# caretaker-rotaryknob.net
KiCad netlist of a schematic drawn in EAGLE
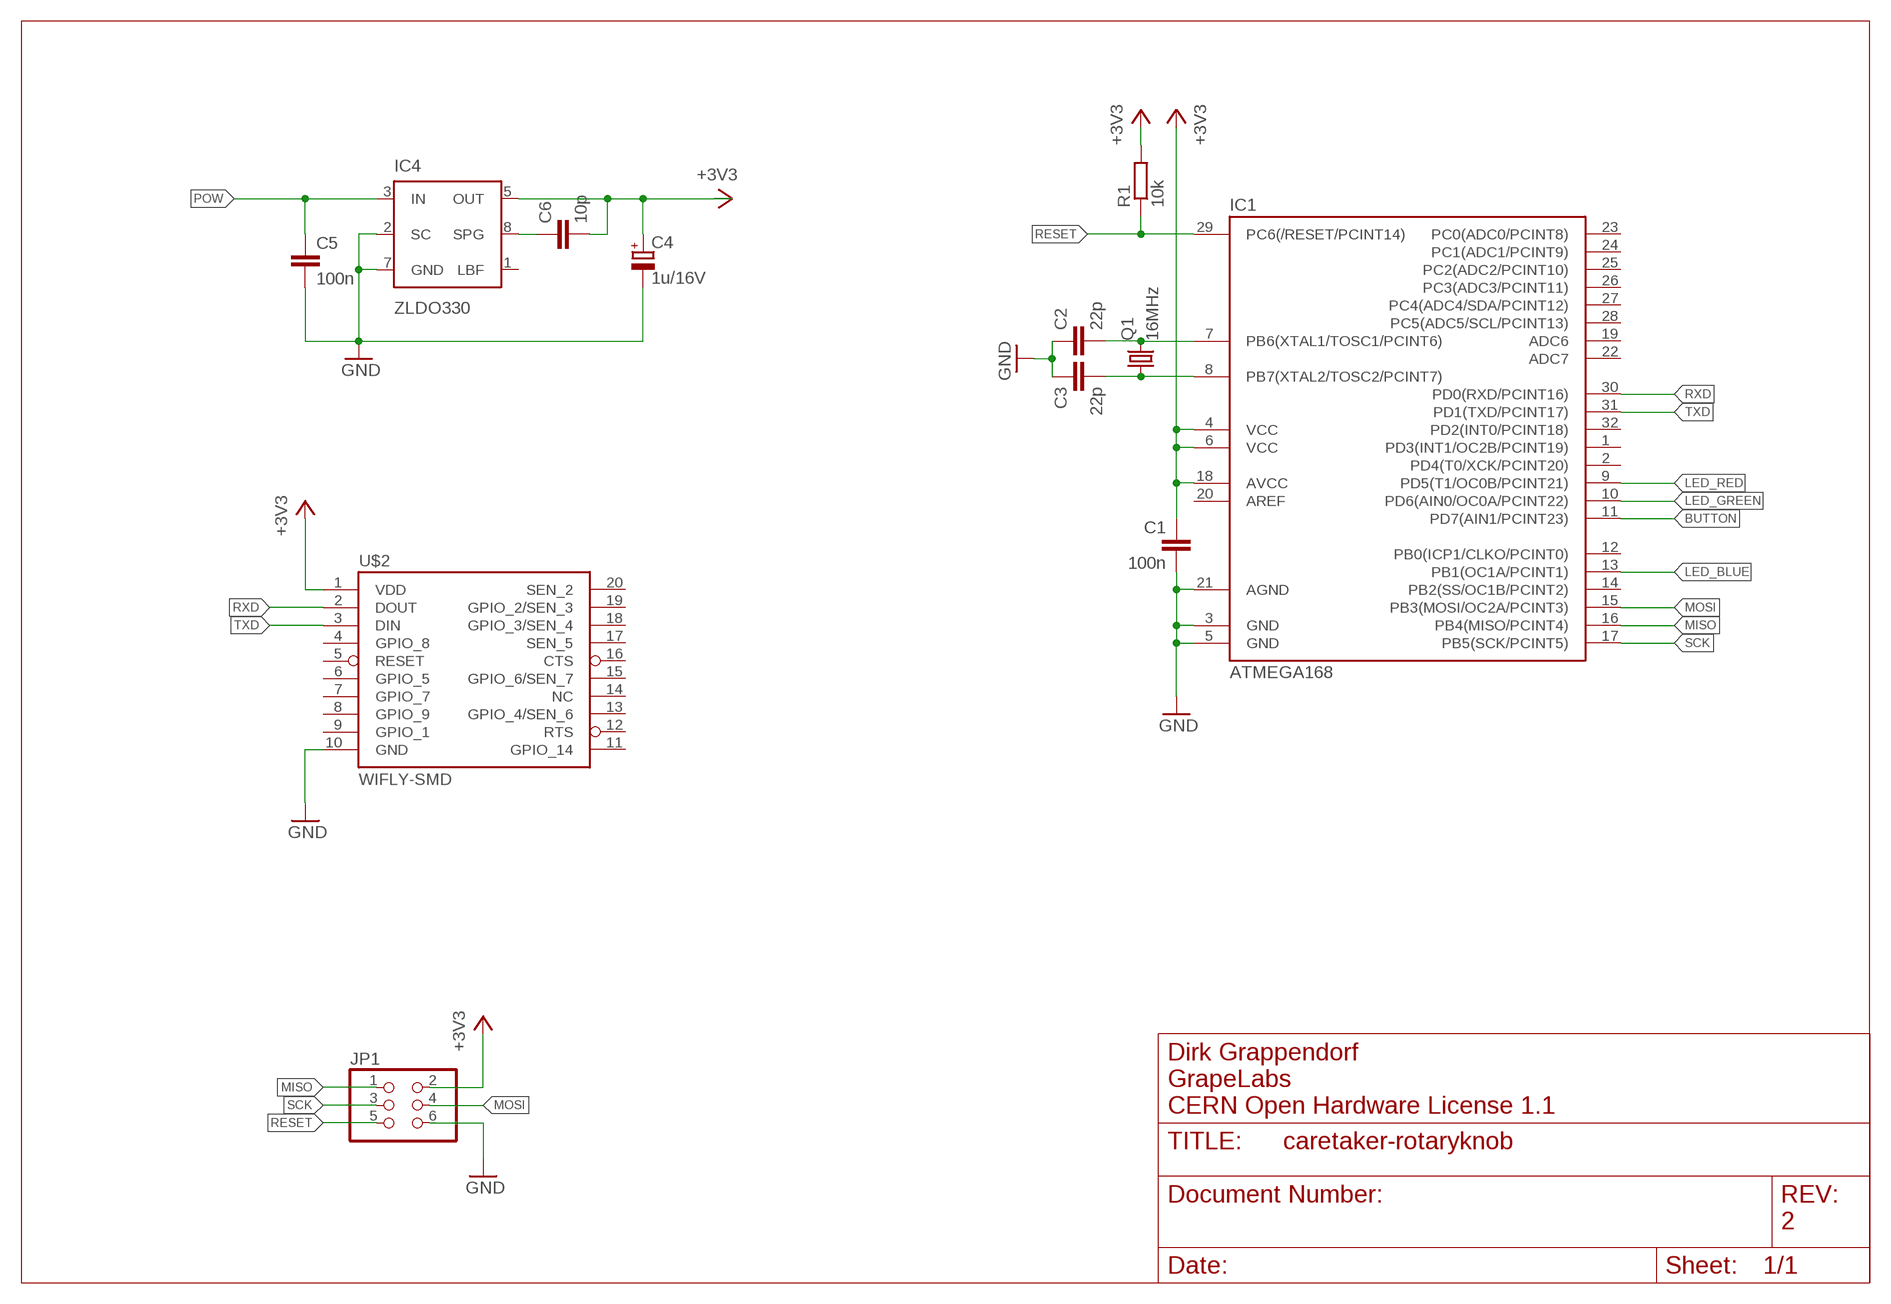
[diagram p0: schematic, sheet 1]

(export (version "E")
  (design (tool "Eeschema 10.0.6"))
  (components
    (comp (ref "C1")
      (value "100n")
      (footprint "eagle-import:C1206K")
      (libsource (lib "eagle-import") (part "C-EUC1206K"))
    )
    (comp (ref "C2")
      (value "22p")
      (footprint "eagle-import:C1206K")
      (libsource (lib "eagle-import") (part "C-EUC1206K"))
    )
    (comp (ref "C3")
      (value "22p")
      (footprint "eagle-import:C1206K")
      (libsource (lib "eagle-import") (part "C-EUC1206K"))
    )
    (comp (ref "C4")
      (value "1u/16V")
      (footprint "eagle-import:PANASONIC_B")
      (libsource (lib "eagle-import") (part "CPOL-EUB"))
    )
    (comp (ref "C5")
      (value "100n")
      (footprint "eagle-import:C1206")
      (libsource (lib "eagle-import") (part "C-EUC1206"))
    )
    (comp (ref "C6")
      (value "10p")
      (footprint "eagle-import:C1206")
      (libsource (lib "eagle-import") (part "C-EUC1206"))
    )
    (comp (ref "IC1")
      (value "ATMEGA168")
      (footprint "eagle-import:TQFP32-08")
      (libsource (lib "eagle-import") (part "ATMEGA48/88/168-AU"))
    )
    (comp (ref "IC4")
      (value "ZLDO330")
      (footprint "eagle-import:SM8")
      (libsource (lib "eagle-import") (part "ZLDO330"))
    )
    (comp (ref "JP1")
      (value "PINHD-2X3_2.54-SMD")
      (footprint "eagle-import:2X03SMD")
      (libsource (lib "eagle-import") (part "PINHD-2X3_2.54-SMD"))
    )
    (comp (ref "Q1")
      (value "16MHz")
      (footprint "eagle-import:HC49UP")
      (libsource (lib "eagle-import") (part "CRYSTALHC49UP"))
    )
    (comp (ref "R1")
      (value "10k")
      (footprint "eagle-import:M1206")
      (libsource (lib "eagle-import") (part "R-EU_M1206"))
    )
    (comp (ref "U$2")
      (value "WIFLY-SMD")
      (footprint "eagle-import:WIFLY-SMD")
      (libsource (lib "eagle-import") (part "WIFLY-SMD"))
    )
  )
  (nets
    (net (code "1") (name "+3V3") (class "Default")
      (node (ref "C1") (pin "1") (pinfunction "1_1") (pintype "passive"))
      (node (ref "C4") (pin "+") (pinfunction "+_+") (pintype "passive"))
      (node (ref "C6") (pin "2") (pinfunction "2_2") (pintype "passive"))
      (node (ref "IC1") (pin "18") (pinfunction "AVCC_18") (pintype "passive"))
      (node (ref "IC1") (pin "4") (pinfunction "VCC_4") (pintype "power_in"))
      (node (ref "IC1") (pin "6") (pinfunction "VCC_6") (pintype "power_in"))
      (node (ref "IC4") (pin "5") (pinfunction "OUT_5") (pintype "output"))
      (node (ref "JP1") (pin "2") (pinfunction "2_2") (pintype "passive"))
      (node (ref "R1") (pin "2") (pinfunction "2_2") (pintype "passive"))
      (node (ref "U$2") (pin "1") (pinfunction "VDD_1") (pintype "power_in"))
    )
    (net (code "2") (name "BUTTON") (class "Default")
      (node (ref "IC1") (pin "11") (pinfunction "PD7(AIN1/PCINT23)_11") (pintype "bidirectional"))
    )
    (net (code "3") (name "GND") (class "Default")
      (node (ref "C1") (pin "2") (pinfunction "2_2") (pintype "passive"))
      (node (ref "C2") (pin "1") (pinfunction "1_1") (pintype "passive"))
      (node (ref "C3") (pin "1") (pinfunction "1_1") (pintype "passive"))
      (node (ref "C4") (pin "-") (pinfunction "-_-") (pintype "passive"))
      (node (ref "C5") (pin "2") (pinfunction "2_2") (pintype "passive"))
      (node (ref "IC1") (pin "21") (pinfunction "AGND_21") (pintype "power_in"))
      (node (ref "IC1") (pin "3") (pinfunction "GND_3") (pintype "power_in"))
      (node (ref "IC1") (pin "5") (pinfunction "GND_5") (pintype "power_in"))
      (node (ref "IC4") (pin "2") (pinfunction "SC_2") (pintype "input"))
      (node (ref "IC4") (pin "7") (pinfunction "GND_7") (pintype "power_in"))
      (node (ref "JP1") (pin "6") (pinfunction "6_6") (pintype "passive"))
      (node (ref "U$2") (pin "10") (pinfunction "GND_10") (pintype "power_in"))
    )
    (net (code "4") (name "LED_BLUE") (class "Default")
      (node (ref "IC1") (pin "13") (pinfunction "PB1(OC1A/PCINT1)_13") (pintype "bidirectional"))
    )
    (net (code "5") (name "LED_GREEN") (class "Default")
      (node (ref "IC1") (pin "10") (pinfunction "PD6(AIN0/OC0A/PCINT22)_10") (pintype "bidirectional"))
    )
    (net (code "6") (name "LED_RED") (class "Default")
      (node (ref "IC1") (pin "9") (pinfunction "PD5(T1/OC0B/PCINT21)_9") (pintype "bidirectional"))
    )
    (net (code "7") (name "MISO") (class "Default")
      (node (ref "IC1") (pin "16") (pinfunction "PB4(MISO/PCINT4)_16") (pintype "bidirectional"))
      (node (ref "JP1") (pin "1") (pinfunction "1_1") (pintype "passive"))
    )
    (net (code "8") (name "MOSI") (class "Default")
      (node (ref "IC1") (pin "15") (pinfunction "PB3(MOSI/OC2A/PCINT3)_15") (pintype "bidirectional"))
      (node (ref "JP1") (pin "4") (pinfunction "4_4") (pintype "passive"))
    )
    (net (code "9") (name "Net-(IC1-PB6(XTAL1{slash}TOSC1{slash}PCINT6))") (class "Default")
      (node (ref "C2") (pin "2") (pinfunction "2_2") (pintype "passive"))
      (node (ref "IC1") (pin "7") (pinfunction "PB6(XTAL1/TOSC1/PCINT6)_7") (pintype "bidirectional"))
      (node (ref "Q1") (pin "2") (pinfunction "2_2") (pintype "passive"))
    )
    (net (code "10") (name "Net-(IC1-PB7(XTAL2{slash}TOSC2{slash}PCINT7))") (class "Default")
      (node (ref "C3") (pin "2") (pinfunction "2_2") (pintype "passive"))
      (node (ref "IC1") (pin "8") (pinfunction "PB7(XTAL2/TOSC2/PCINT7)_8") (pintype "bidirectional"))
      (node (ref "Q1") (pin "1") (pinfunction "1_1") (pintype "passive"))
    )
    (net (code "11") (name "Net-(IC4-SPG)") (class "Default")
      (node (ref "C6") (pin "1") (pinfunction "1_1") (pintype "passive"))
      (node (ref "IC4") (pin "8") (pinfunction "SPG_8") (pintype "input"))
    )
    (net (code "12") (name "POW") (class "Default")
      (node (ref "C5") (pin "1") (pinfunction "1_1") (pintype "passive"))
      (node (ref "IC4") (pin "3") (pinfunction "IN_3") (pintype "input"))
    )
    (net (code "13") (name "RESET") (class "Default")
      (node (ref "IC1") (pin "29") (pinfunction "PC6(/RESET/PCINT14)_29") (pintype "bidirectional"))
      (node (ref "JP1") (pin "5") (pinfunction "5_5") (pintype "passive"))
      (node (ref "R1") (pin "1") (pinfunction "1_1") (pintype "passive"))
    )
    (net (code "14") (name "RXD") (class "Default")
      (node (ref "IC1") (pin "30") (pinfunction "PD0(RXD/PCINT16)_30") (pintype "bidirectional"))
      (node (ref "U$2") (pin "2") (pinfunction "DOUT_2") (pintype "output"))
    )
    (net (code "15") (name "SCK") (class "Default")
      (node (ref "IC1") (pin "17") (pinfunction "PB5(SCK/PCINT5)_17") (pintype "bidirectional"))
      (node (ref "JP1") (pin "3") (pinfunction "3_3") (pintype "passive"))
    )
    (net (code "16") (name "TXD") (class "Default")
      (node (ref "IC1") (pin "31") (pinfunction "PD1(TXD/PCINT17)_31") (pintype "bidirectional"))
      (node (ref "U$2") (pin "3") (pinfunction "DIN_3") (pintype "input"))
    )
    (net (code "17") (name "unconnected-(IC1-ADC6-Pad19)") (class "Default")
      (node (ref "IC1") (pin "19") (pinfunction "ADC6_19") (pintype "passive"))
    )
    (net (code "18") (name "unconnected-(IC1-ADC7-Pad22)") (class "Default")
      (node (ref "IC1") (pin "22") (pinfunction "ADC7_22") (pintype "passive"))
    )
    (net (code "19") (name "unconnected-(IC1-AREF-Pad20)") (class "Default")
      (node (ref "IC1") (pin "20") (pinfunction "AREF_20") (pintype "passive"))
    )
    (net (code "20") (name "unconnected-(IC1-PB0(ICP1{slash}CLKO{slash}PCINT0)-Pad12)") (class "Default")
      (node (ref "IC1") (pin "12") (pinfunction "PB0(ICP1/CLKO/PCINT0)_12") (pintype "bidirectional"))
    )
    (net (code "21") (name "unconnected-(IC1-PB2(SS{slash}OC1B{slash}PCINT2)-Pad14)") (class "Default")
      (node (ref "IC1") (pin "14") (pinfunction "PB2(SS/OC1B/PCINT2)_14") (pintype "bidirectional"))
    )
    (net (code "22") (name "unconnected-(IC1-PC0(ADC0{slash}PCINT8)-Pad23)") (class "Default")
      (node (ref "IC1") (pin "23") (pinfunction "PC0(ADC0/PCINT8)_23") (pintype "bidirectional"))
    )
    (net (code "23") (name "unconnected-(IC1-PC1(ADC1{slash}PCINT9)-Pad24)") (class "Default")
      (node (ref "IC1") (pin "24") (pinfunction "PC1(ADC1/PCINT9)_24") (pintype "bidirectional"))
    )
    (net (code "24") (name "unconnected-(IC1-PC2(ADC2{slash}PCINT10)-Pad25)") (class "Default")
      (node (ref "IC1") (pin "25") (pinfunction "PC2(ADC2/PCINT10)_25") (pintype "bidirectional"))
    )
    (net (code "25") (name "unconnected-(IC1-PC3(ADC3{slash}PCINT11)-Pad26)") (class "Default")
      (node (ref "IC1") (pin "26") (pinfunction "PC3(ADC3/PCINT11)_26") (pintype "bidirectional"))
    )
    (net (code "26") (name "unconnected-(IC1-PC4(ADC4{slash}SDA{slash}PCINT12)-Pad27)") (class "Default")
      (node (ref "IC1") (pin "27") (pinfunction "PC4(ADC4/SDA/PCINT12)_27") (pintype "bidirectional"))
    )
    (net (code "27") (name "unconnected-(IC1-PC5(ADC5{slash}SCL{slash}PCINT13)-Pad28)") (class "Default")
      (node (ref "IC1") (pin "28") (pinfunction "PC5(ADC5/SCL/PCINT13)_28") (pintype "bidirectional"))
    )
    (net (code "28") (name "unconnected-(IC1-PD2(INT0{slash}PCINT18)-Pad32)") (class "Default")
      (node (ref "IC1") (pin "32") (pinfunction "PD2(INT0/PCINT18)_32") (pintype "bidirectional"))
    )
    (net (code "29") (name "unconnected-(IC1-PD3(INT1{slash}OC2B{slash}PCINT19)-Pad1)") (class "Default")
      (node (ref "IC1") (pin "1") (pinfunction "PD3(INT1/OC2B/PCINT19)_1") (pintype "bidirectional"))
    )
    (net (code "30") (name "unconnected-(IC1-PD4(T0{slash}XCK{slash}PCINT20)-Pad2)") (class "Default")
      (node (ref "IC1") (pin "2") (pinfunction "PD4(T0/XCK/PCINT20)_2") (pintype "bidirectional"))
    )
    (net (code "31") (name "unconnected-(IC4-LBF-Pad1)") (class "Default")
      (node (ref "IC4") (pin "1") (pinfunction "LBF_1") (pintype "output"))
    )
    (net (code "32") (name "unconnected-(U$2-CTS-Pad16)") (class "Default")
      (node (ref "U$2") (pin "16") (pinfunction "CTS_16") (pintype "input"))
    )
    (net (code "33") (name "unconnected-(U$2-GPIO_1-Pad9)") (class "Default")
      (node (ref "U$2") (pin "9") (pinfunction "GPIO_1_9") (pintype "bidirectional"))
    )
    (net (code "34") (name "unconnected-(U$2-GPIO_2{slash}SEN_3-Pad19)") (class "Default")
      (node (ref "U$2") (pin "19") (pinfunction "GPIO_2/SEN_3_19") (pintype "bidirectional"))
    )
    (net (code "35") (name "unconnected-(U$2-GPIO_3{slash}SEN_4-Pad18)") (class "Default")
      (node (ref "U$2") (pin "18") (pinfunction "GPIO_3/SEN_4_18") (pintype "bidirectional"))
    )
    (net (code "36") (name "unconnected-(U$2-GPIO_4{slash}SEN_6-Pad13)") (class "Default")
      (node (ref "U$2") (pin "13") (pinfunction "GPIO_4/SEN_6_13") (pintype "bidirectional"))
    )
    (net (code "37") (name "unconnected-(U$2-GPIO_5-Pad6)") (class "Default")
      (node (ref "U$2") (pin "6") (pinfunction "GPIO_5_6") (pintype "bidirectional"))
    )
    (net (code "38") (name "unconnected-(U$2-GPIO_6{slash}SEN_7-Pad15)") (class "Default")
      (node (ref "U$2") (pin "15") (pinfunction "GPIO_6/SEN_7_15") (pintype "bidirectional"))
    )
    (net (code "39") (name "unconnected-(U$2-GPIO_7-Pad7)") (class "Default")
      (node (ref "U$2") (pin "7") (pinfunction "GPIO_7_7") (pintype "bidirectional"))
    )
    (net (code "40") (name "unconnected-(U$2-GPIO_8-Pad4)") (class "Default")
      (node (ref "U$2") (pin "4") (pinfunction "GPIO_8_4") (pintype "bidirectional"))
    )
    (net (code "41") (name "unconnected-(U$2-GPIO_9-Pad8)") (class "Default")
      (node (ref "U$2") (pin "8") (pinfunction "GPIO_9_8") (pintype "bidirectional"))
    )
    (net (code "42") (name "unconnected-(U$2-GPIO_14-Pad11)") (class "Default")
      (node (ref "U$2") (pin "11") (pinfunction "GPIO_14_11") (pintype "bidirectional"))
    )
    (net (code "43") (name "unconnected-(U$2-NC-Pad14)") (class "Default")
      (node (ref "U$2") (pin "14") (pinfunction "NC_14") (pintype "bidirectional"))
    )
    (net (code "44") (name "unconnected-(U$2-RESET-Pad5)") (class "Default")
      (node (ref "U$2") (pin "5") (pinfunction "RESET_5") (pintype "input"))
    )
    (net (code "45") (name "unconnected-(U$2-RTS-Pad12)") (class "Default")
      (node (ref "U$2") (pin "12") (pinfunction "RTS_12") (pintype "output"))
    )
    (net (code "46") (name "unconnected-(U$2-SEN_2-Pad20)") (class "Default")
      (node (ref "U$2") (pin "20") (pinfunction "SEN_2_20") (pintype "bidirectional"))
    )
    (net (code "47") (name "unconnected-(U$2-SEN_5-Pad17)") (class "Default")
      (node (ref "U$2") (pin "17") (pinfunction "SEN_5_17") (pintype "bidirectional"))
    )
  )
)
